# PowerBoard.net
KiCad netlist of a schematic drawn in EAGLE
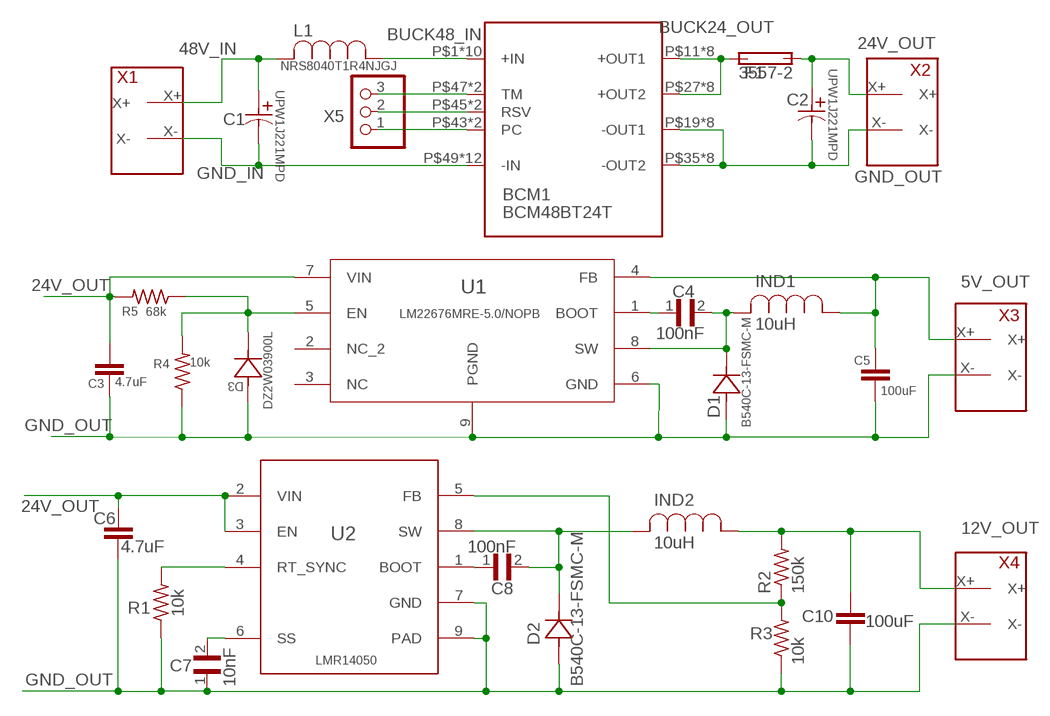
[diagram p0: schematic, sheet 1]

(export (version "E")
  (design (tool "Eeschema 10.0.6"))
  (components
    (comp (ref "BCM1")
      (value "BCM48BT24T")
      (footprint "eagle-import:BCM48BT24T")
      (libsource (lib "eagle-import") (part "BCM48BT24T"))
    )
    (comp (ref "C1")
      (value "UPW1J221MPD")
      (footprint "eagle-import:PCAP_10X20-THRU-ELECT")
      (libsource (lib "eagle-import") (part "UPW1J221MPD"))
    )
    (comp (ref "C2")
      (value "UPW1J221MPD")
      (footprint "eagle-import:PCAP_10X20-THRU-ELECT")
      (libsource (lib "eagle-import") (part "UPW1J221MPD"))
    )
    (comp (ref "C3")
      (value "4.7uF")
      (footprint "eagle-import:0603")
      (libsource (lib "eagle-import") (part "4.7UF0603"))
    )
    (comp (ref "C4")
      (value "100nF")
      (footprint "eagle-import:CAPC2012X135N")
      (fields (field (name "MF") "Murata Electronics") (field (name "MP") "GRM21BR60E107ME15L"))
      (libsource (lib "eagle-import") (part "GRM21BR60E107ME15L"))
    )
    (comp (ref "C5")
      (value "100uF")
      (footprint "eagle-import:1210")
      (libsource (lib "eagle-import") (part "10UF-1210-50V-20%"))
    )
    (comp (ref "C6")
      (value "4.7uF")
      (footprint "eagle-import:0603")
      (libsource (lib "eagle-import") (part "4.7UF0603"))
    )
    (comp (ref "C7")
      (value "10nF")
      (footprint "eagle-import:CAPC2012X135N")
      (fields (field (name "MF") "Murata Electronics") (field (name "MP") "GRM21BR60E107ME15L"))
      (libsource (lib "eagle-import") (part "GRM21BR60E107ME15L"))
    )
    (comp (ref "C8")
      (value "100nF")
      (footprint "eagle-import:CAPC2012X135N")
      (fields (field (name "MF") "Murata Electronics") (field (name "MP") "GRM21BR60E107ME15L"))
      (libsource (lib "eagle-import") (part "GRM21BR60E107ME15L"))
    )
    (comp (ref "C10")
      (value "100uF")
      (footprint "eagle-import:1210")
      (libsource (lib "eagle-import") (part "10UF-1210-50V-20%"))
    )
    (comp (ref "D1")
      (value "B540C-13-FSMC-M")
      (footprint "eagle-import:SMC-M")
      (fields (field (name "MANUFACTURER_PART_NUMBER") "B540C13F"))
      (libsource (lib "eagle-import") (part "B540C-13-FSMC-M"))
    )
    (comp (ref "D2")
      (value "B540C-13-FSMC-M")
      (footprint "eagle-import:SMC-M")
      (fields (field (name "MANUFACTURER_PART_NUMBER") "B540C13F"))
      (libsource (lib "eagle-import") (part "B540C-13-FSMC-M"))
    )
    (comp (ref "D3")
      (value "DZ2W03900L")
      (footprint "eagle-import:MINI2-F3-B")
      (libsource (lib "eagle-import") (part "DZ2W03900L"))
    )
    (comp (ref "F1")
      (value "3557-2")
      (footprint "eagle-import:FUSE_3557-2")
      (fields (field (name "MF") "Keystone"))
      (libsource (lib "eagle-import") (part "3557-2"))
    )
    (comp (ref "IND1")
      (value "10uH")
      (footprint "eagle-import:11.15X10")
      (libsource (lib "eagle-import") (part "ASPI-1040HIA"))
    )
    (comp (ref "IND2")
      (value "10uH")
      (footprint "eagle-import:11.15X10")
      (libsource (lib "eagle-import") (part "ASPI-1040HIA"))
    )
    (comp (ref "L1")
      (value "NRS8040T1R4NJGJ")
      (footprint "eagle-import:IND_TAIYO_NRS8040")
      (libsource (lib "eagle-import") (part "NRS8040T1R4NJGJ"))
    )
    (comp (ref "R1")
      (value "10k")
      (footprint "eagle-import:R0603")
      (libsource (lib "eagle-import") (part "R-US_R0603"))
    )
    (comp (ref "R2")
      (value "150k")
      (footprint "eagle-import:R0603")
      (libsource (lib "eagle-import") (part "R-US_R0603"))
    )
    (comp (ref "R3")
      (value "10k")
      (footprint "eagle-import:R0603")
      (libsource (lib "eagle-import") (part "R-US_R0603"))
    )
    (comp (ref "R4")
      (value "10k")
      (footprint "eagle-import:R0603")
      (libsource (lib "eagle-import") (part "R-US_R0603"))
    )
    (comp (ref "R5")
      (value "68k")
      (footprint "eagle-import:R0603")
      (libsource (lib "eagle-import") (part "R-US_R0603"))
    )
    (comp (ref "U1")
      (value "LM22676MRE-5.0/NOPB")
      (footprint "eagle-import:MRA08B")
      (fields (field (name "MANUFACTURER_PART_NUMBER") "LM22676MRE5.0NOPB"))
      (libsource (lib "eagle-import") (part "LM22676MRE-5.0/NOPB"))
    )
    (comp (ref "U2")
      (value "LMR14050")
      (footprint "eagle-import:DDA0008E_N")
      (fields
        (field (name "MANUFACTURER") "Texas Instruments")
        (field (name "MANUFACTURER_PART_NUMBER") "LMR14050SDDAR")
      )
      (libsource (lib "eagle-import") (part "LMR14050SDDAR"))
    )
    (comp (ref "X1")
      (value "XT30U-M")
      (footprint "eagle-import:XT30")
      (libsource (lib "eagle-import") (part "XT30U-M"))
    )
    (comp (ref "X2")
      (value "XT30U-M")
      (footprint "eagle-import:XT30")
      (libsource (lib "eagle-import") (part "XT30U-M"))
    )
    (comp (ref "X3")
      (value "XT30U-M")
      (footprint "eagle-import:XT30")
      (libsource (lib "eagle-import") (part "XT30U-M"))
    )
    (comp (ref "X4")
      (value "XT30U-M")
      (footprint "eagle-import:XT30")
      (libsource (lib "eagle-import") (part "XT30U-M"))
    )
    (comp (ref "X5")
      (value "9-146281-0")
      (footprint "eagle-import:TE_9-146281-0")
      (fields (field (name "MF") "TE Connectivity"))
      (libsource (lib "eagle-import") (part "9-146281-0"))
    )
  )
  (nets
    (net (code "1") (name "/5V_OUT") (class "Default")
      (node (ref "C5") (pin "1") (pinfunction "1_1") (pintype "passive"))
      (node (ref "IND1") (pin "1") (pinfunction "1_1") (pintype "passive"))
      (node (ref "U1") (pin "4") (pinfunction "FB_4") (pintype "input"))
      (node (ref "X3") (pin "X+") (pinfunction "X+_X+") (pintype "bidirectional"))
    )
    (net (code "2") (name "/12V_OUT") (class "Default")
      (node (ref "C10") (pin "1") (pinfunction "1_1") (pintype "passive"))
      (node (ref "IND2") (pin "1") (pinfunction "1_1") (pintype "passive"))
      (node (ref "R2") (pin "2") (pinfunction "2_2") (pintype "passive"))
      (node (ref "X4") (pin "X+") (pinfunction "X+_X+") (pintype "bidirectional"))
    )
    (net (code "3") (name "/24V_OUT") (class "Default")
      (node (ref "C2") (pin "1") (pinfunction "11_1") (pintype "passive"))
      (node (ref "C3") (pin "1") (pinfunction "1_1") (pintype "passive"))
      (node (ref "C6") (pin "1") (pinfunction "1_1") (pintype "passive"))
      (node (ref "F1") (pin "3") (pinfunction "2A_3") (pintype "passive"))
      (node (ref "F1") (pin "4") (pinfunction "2A_4") (pintype "passive"))
      (node (ref "R5") (pin "2") (pinfunction "2_2") (pintype "passive"))
      (node (ref "U1") (pin "7") (pinfunction "VIN_7") (pintype "power_in"))
      (node (ref "U2") (pin "2") (pinfunction "VIN_2") (pintype "power_in"))
      (node (ref "U2") (pin "3") (pinfunction "EN_3") (pintype "input"))
      (node (ref "X2") (pin "X+") (pinfunction "X+_X+") (pintype "bidirectional"))
    )
    (net (code "4") (name "/48V_IN") (class "Default")
      (node (ref "C1") (pin "1") (pinfunction "11_1") (pintype "passive"))
      (node (ref "L1") (pin "2") (pinfunction "2_2") (pintype "passive"))
      (node (ref "X1") (pin "X+") (pinfunction "X+_X+") (pintype "bidirectional"))
    )
    (net (code "5") (name "/BUCK24_OUT") (class "Default")
      (node (ref "BCM1") (pin "P$11") (pinfunction "+OUT1_P$11") (pintype "output"))
      (node (ref "BCM1") (pin "P$12") (pinfunction "+OUT1_P$12") (pintype "output"))
      (node (ref "BCM1") (pin "P$13") (pinfunction "+OUT1_P$13") (pintype "output"))
      (node (ref "BCM1") (pin "P$14") (pinfunction "+OUT1_P$14") (pintype "output"))
      (node (ref "BCM1") (pin "P$15") (pinfunction "+OUT1_P$15") (pintype "output"))
      (node (ref "BCM1") (pin "P$16") (pinfunction "+OUT1_P$16") (pintype "output"))
      (node (ref "BCM1") (pin "P$17") (pinfunction "+OUT1_P$17") (pintype "output"))
      (node (ref "BCM1") (pin "P$18") (pinfunction "+OUT1_P$18") (pintype "output"))
      (node (ref "BCM1") (pin "P$27") (pinfunction "+OUT2_P$27") (pintype "output"))
      (node (ref "BCM1") (pin "P$28") (pinfunction "+OUT2_P$28") (pintype "output"))
      (node (ref "BCM1") (pin "P$29") (pinfunction "+OUT2_P$29") (pintype "output"))
      (node (ref "BCM1") (pin "P$30") (pinfunction "+OUT2_P$30") (pintype "output"))
      (node (ref "BCM1") (pin "P$31") (pinfunction "+OUT2_P$31") (pintype "output"))
      (node (ref "BCM1") (pin "P$32") (pinfunction "+OUT2_P$32") (pintype "output"))
      (node (ref "BCM1") (pin "P$33") (pinfunction "+OUT2_P$33") (pintype "output"))
      (node (ref "BCM1") (pin "P$34") (pinfunction "+OUT2_P$34") (pintype "output"))
      (node (ref "F1") (pin "1") (pinfunction "1A_1") (pintype "passive"))
      (node (ref "F1") (pin "2") (pinfunction "1A_2") (pintype "passive"))
    )
    (net (code "6") (name "/BUCK48_IN") (class "Default")
      (node (ref "BCM1") (pin "P$1") (pinfunction "+IN_P$1") (pintype "input"))
      (node (ref "BCM1") (pin "P$10") (pinfunction "+IN_P$10") (pintype "input"))
      (node (ref "BCM1") (pin "P$2") (pinfunction "+IN_P$2") (pintype "input"))
      (node (ref "BCM1") (pin "P$3") (pinfunction "+IN_P$3") (pintype "input"))
      (node (ref "BCM1") (pin "P$4") (pinfunction "+IN_P$4") (pintype "input"))
      (node (ref "BCM1") (pin "P$5") (pinfunction "+IN_P$5") (pintype "input"))
      (node (ref "BCM1") (pin "P$6") (pinfunction "+IN_P$6") (pintype "input"))
      (node (ref "BCM1") (pin "P$7") (pinfunction "+IN_P$7") (pintype "input"))
      (node (ref "BCM1") (pin "P$8") (pinfunction "+IN_P$8") (pintype "input"))
      (node (ref "BCM1") (pin "P$9") (pinfunction "+IN_P$9") (pintype "input"))
      (node (ref "L1") (pin "1") (pinfunction "1_1") (pintype "passive"))
    )
    (net (code "7") (name "/GND_IN") (class "Default")
      (node (ref "BCM1") (pin "P$49") (pinfunction "-IN_P$49") (pintype "input"))
      (node (ref "BCM1") (pin "P$50") (pinfunction "-IN_P$50") (pintype "input"))
      (node (ref "BCM1") (pin "P$51") (pinfunction "-IN_P$51") (pintype "input"))
      (node (ref "BCM1") (pin "P$52") (pinfunction "-IN_P$52") (pintype "input"))
      (node (ref "BCM1") (pin "P$53") (pinfunction "-IN_P$53") (pintype "input"))
      (node (ref "BCM1") (pin "P$54") (pinfunction "-IN_P$54") (pintype "input"))
      (node (ref "BCM1") (pin "P$55") (pinfunction "-IN_P$55") (pintype "input"))
      (node (ref "BCM1") (pin "P$56") (pinfunction "-IN_P$56") (pintype "input"))
      (node (ref "BCM1") (pin "P$57") (pinfunction "-IN_P$57") (pintype "input"))
      (node (ref "BCM1") (pin "P$58") (pinfunction "-IN_P$58") (pintype "input"))
      (node (ref "BCM1") (pin "P$59") (pinfunction "-IN_P$59") (pintype "input"))
      (node (ref "BCM1") (pin "P$60") (pinfunction "-IN_P$60") (pintype "input"))
      (node (ref "C1") (pin "2") (pinfunction "22_2") (pintype "passive"))
      (node (ref "X1") (pin "X-") (pinfunction "X-_X-") (pintype "bidirectional"))
    )
    (net (code "8") (name "/GND_OUT") (class "Default")
      (node (ref "BCM1") (pin "P$19") (pinfunction "-OUT1_P$19") (pintype "output"))
      (node (ref "BCM1") (pin "P$20") (pinfunction "-OUT1_P$20") (pintype "output"))
      (node (ref "BCM1") (pin "P$21") (pinfunction "-OUT1_P$21") (pintype "output"))
      (node (ref "BCM1") (pin "P$22") (pinfunction "-OUT1_P$22") (pintype "output"))
      (node (ref "BCM1") (pin "P$23") (pinfunction "-OUT1_P$23") (pintype "output"))
      (node (ref "BCM1") (pin "P$24") (pinfunction "-OUT1_P$24") (pintype "output"))
      (node (ref "BCM1") (pin "P$25") (pinfunction "-OUT1_P$25") (pintype "output"))
      (node (ref "BCM1") (pin "P$26") (pinfunction "-OUT1_P$26") (pintype "output"))
      (node (ref "BCM1") (pin "P$35") (pinfunction "-OUT2_P$35") (pintype "output"))
      (node (ref "BCM1") (pin "P$36") (pinfunction "-OUT2_P$36") (pintype "output"))
      (node (ref "BCM1") (pin "P$37") (pinfunction "-OUT2_P$37") (pintype "output"))
      (node (ref "BCM1") (pin "P$38") (pinfunction "-OUT2_P$38") (pintype "output"))
      (node (ref "BCM1") (pin "P$39") (pinfunction "-OUT2_P$39") (pintype "output"))
      (node (ref "BCM1") (pin "P$40") (pinfunction "-OUT2_P$40") (pintype "output"))
      (node (ref "BCM1") (pin "P$41") (pinfunction "-OUT2_P$41") (pintype "output"))
      (node (ref "BCM1") (pin "P$42") (pinfunction "-OUT2_P$42") (pintype "output"))
      (node (ref "C10") (pin "2") (pinfunction "2_2") (pintype "passive"))
      (node (ref "C2") (pin "2") (pinfunction "22_2") (pintype "passive"))
      (node (ref "C3") (pin "2") (pinfunction "2_2") (pintype "passive"))
      (node (ref "C5") (pin "2") (pinfunction "2_2") (pintype "passive"))
      (node (ref "C6") (pin "2") (pinfunction "2_2") (pintype "passive"))
      (node (ref "C7") (pin "1") (pinfunction "1_1") (pintype "passive"))
      (node (ref "D1") (pin "2") (pinfunction "21_2") (pintype "passive"))
      (node (ref "D2") (pin "2") (pinfunction "21_2") (pintype "passive"))
      (node (ref "D3") (pin "2") (pinfunction "22_2") (pintype "passive"))
      (node (ref "R1") (pin "1") (pinfunction "1_1") (pintype "passive"))
      (node (ref "R3") (pin "1") (pinfunction "1_1") (pintype "passive"))
      (node (ref "R4") (pin "1") (pinfunction "1_1") (pintype "passive"))
      (node (ref "U1") (pin "6") (pinfunction "GND_6") (pintype "power_in"))
      (node (ref "U1") (pin "9") (pinfunction "PGND_9") (pintype "power_in"))
      (node (ref "U2") (pin "7") (pinfunction "GND_7") (pintype "power_in"))
      (node (ref "U2") (pin "9") (pinfunction "PAD_9") (pintype "power_in"))
      (node (ref "X2") (pin "X-") (pinfunction "X-_X-") (pintype "bidirectional"))
      (node (ref "X3") (pin "X-") (pinfunction "X-_X-") (pintype "bidirectional"))
      (node (ref "X4") (pin "X-") (pinfunction "X-_X-") (pintype "bidirectional"))
    )
    (net (code "9") (name "Net-(BCM1-PC-PadP$43)") (class "Default")
      (node (ref "BCM1") (pin "P$43") (pinfunction "PC_P$43") (pintype "bidirectional"))
      (node (ref "BCM1") (pin "P$44") (pinfunction "PC_P$44") (pintype "bidirectional"))
      (node (ref "X5") (pin "1") (pinfunction "1_1") (pintype "passive"))
    )
    (net (code "10") (name "Net-(BCM1-RSV-PadP$45)") (class "Default")
      (node (ref "BCM1") (pin "P$45") (pinfunction "RSV_P$45") (pintype "bidirectional"))
      (node (ref "BCM1") (pin "P$46") (pinfunction "RSV_P$46") (pintype "bidirectional"))
      (node (ref "X5") (pin "2") (pinfunction "2_2") (pintype "passive"))
    )
    (net (code "11") (name "Net-(BCM1-TM-PadP$47)") (class "Default")
      (node (ref "BCM1") (pin "P$47") (pinfunction "TM_P$47") (pintype "bidirectional"))
      (node (ref "BCM1") (pin "P$48") (pinfunction "TM_P$48") (pintype "bidirectional"))
      (node (ref "X5") (pin "3") (pinfunction "3_3") (pintype "passive"))
    )
    (net (code "12") (name "Net-(D1-12)") (class "Default")
      (node (ref "C4") (pin "2") (pinfunction "2_2") (pintype "passive"))
      (node (ref "D1") (pin "1") (pinfunction "12_1") (pintype "passive"))
      (node (ref "IND1") (pin "2") (pinfunction "2_2") (pintype "passive"))
      (node (ref "U1") (pin "8") (pinfunction "SW_8") (pintype "power_in"))
    )
    (net (code "13") (name "Net-(D2-12)") (class "Default")
      (node (ref "C8") (pin "2") (pinfunction "2_2") (pintype "passive"))
      (node (ref "D2") (pin "1") (pinfunction "12_1") (pintype "passive"))
      (node (ref "IND2") (pin "2") (pinfunction "2_2") (pintype "passive"))
      (node (ref "U2") (pin "8") (pinfunction "SW_8") (pintype "power_in"))
    )
    (net (code "14") (name "Net-(D3-11)") (class "Default")
      (node (ref "D3") (pin "1") (pinfunction "11_1") (pintype "passive"))
      (node (ref "R4") (pin "2") (pinfunction "2_2") (pintype "passive"))
      (node (ref "R5") (pin "1") (pinfunction "1_1") (pintype "passive"))
      (node (ref "U1") (pin "5") (pinfunction "EN_5") (pintype "input"))
    )
    (net (code "15") (name "Net-(U1-BOOT)") (class "Default")
      (node (ref "C4") (pin "1") (pinfunction "1_1") (pintype "passive"))
      (node (ref "U1") (pin "1") (pinfunction "BOOT_1") (pintype "passive"))
    )
    (net (code "16") (name "Net-(U2-BOOT)") (class "Default")
      (node (ref "C8") (pin "1") (pinfunction "1_1") (pintype "passive"))
      (node (ref "U2") (pin "1") (pinfunction "BOOT_1") (pintype "passive"))
    )
    (net (code "17") (name "Net-(U2-FB)") (class "Default")
      (node (ref "R2") (pin "1") (pinfunction "1_1") (pintype "passive"))
      (node (ref "R3") (pin "2") (pinfunction "2_2") (pintype "passive"))
      (node (ref "U2") (pin "5") (pinfunction "FB_5") (pintype "input"))
    )
    (net (code "18") (name "Net-(U2-RT_SYNC)") (class "Default")
      (node (ref "R1") (pin "2") (pinfunction "2_2") (pintype "passive"))
      (node (ref "U2") (pin "4") (pinfunction "RT_SYNC_4") (pintype "passive"))
    )
    (net (code "19") (name "Net-(U2-SS)") (class "Default")
      (node (ref "C7") (pin "2") (pinfunction "2_2") (pintype "passive"))
      (node (ref "U2") (pin "6") (pinfunction "SS_6") (pintype "input"))
    )
    (net (code "20") (name "unconnected-(U1-NC-Pad3)") (class "Default")
      (node (ref "U1") (pin "3") (pinfunction "NC_3") (pintype "passive"))
    )
    (net (code "21") (name "unconnected-(U1-NC_2-Pad2)") (class "Default")
      (node (ref "U1") (pin "2") (pinfunction "NC_2_2") (pintype "passive"))
    )
  )
)
